# BD0004.net
KiCad netlist of a schematic drawn in EAGLE
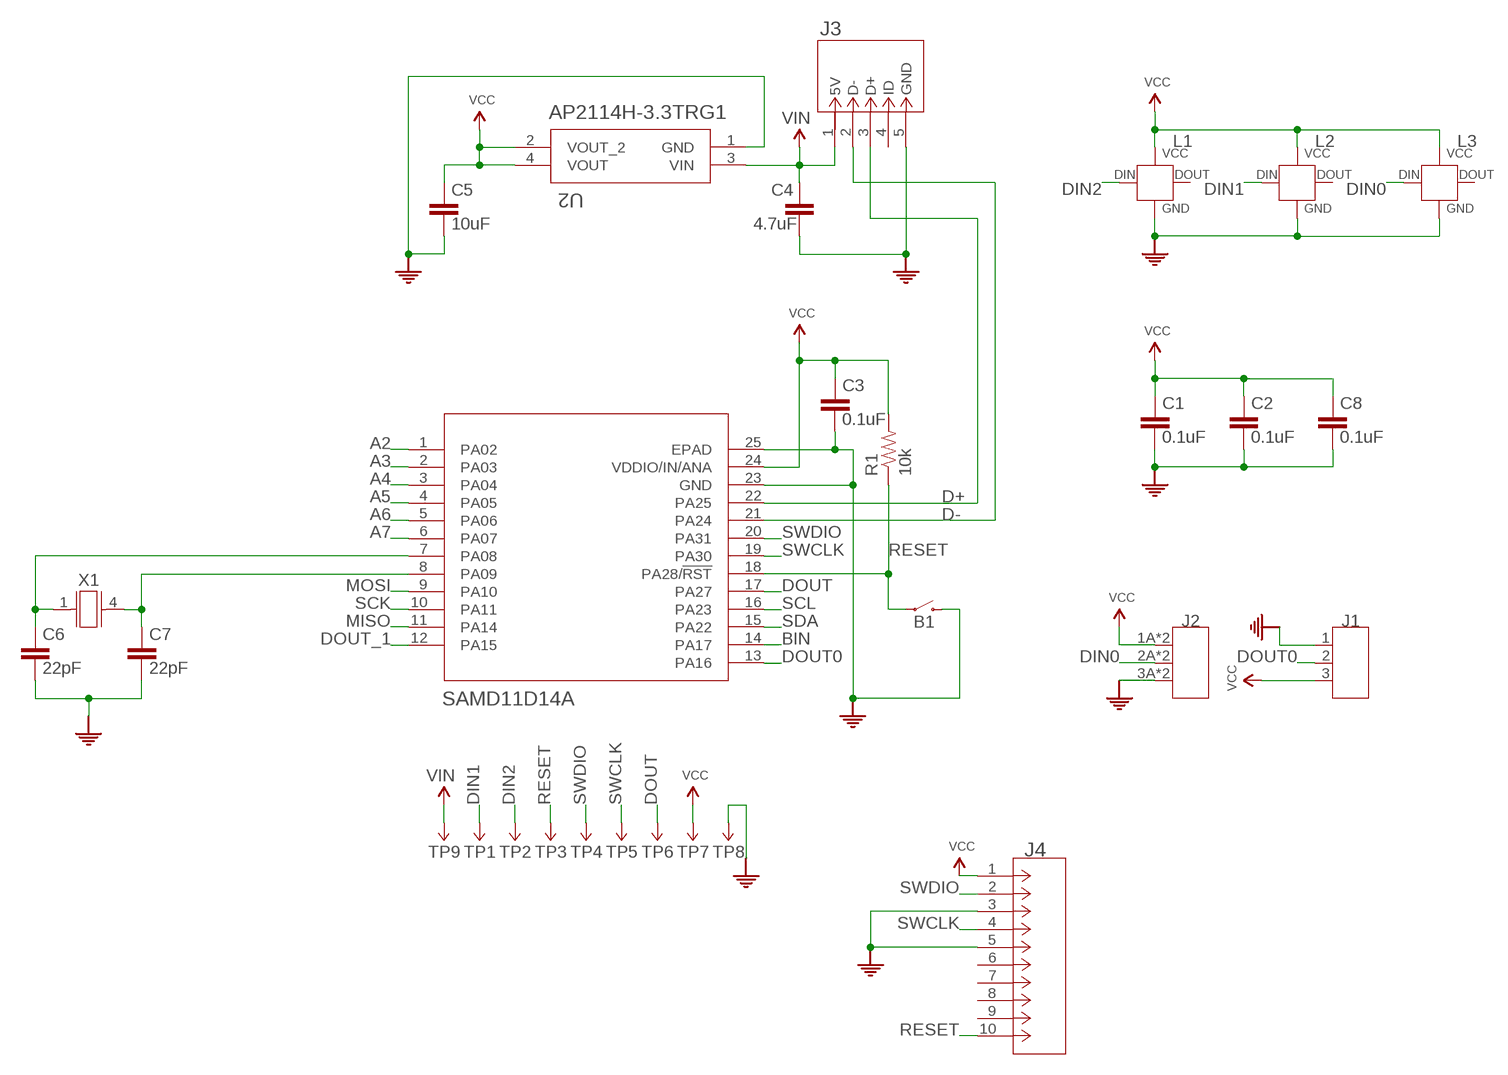
[diagram p0: schematic, sheet 1]

(export (version "E")
  (design (tool "Eeschema 10.0.6"))
  (components
    (comp (ref "B1")
      (value "EVQ-P7A01P")
      (footprint "eagle-import:4-SMD_BUTTON")
      (libsource (lib "eagle-import") (part "EVQ-P7A01P"))
    )
    (comp (ref "C1")
      (value "0.1uF")
      (footprint "eagle-import:0402")
      (libsource (lib "eagle-import") (part "CAPACITOR-0402"))
    )
    (comp (ref "C2")
      (value "0.1uF")
      (footprint "eagle-import:0402")
      (libsource (lib "eagle-import") (part "CAPACITOR-0402"))
    )
    (comp (ref "C3")
      (value "0.1uF")
      (footprint "eagle-import:0402")
      (libsource (lib "eagle-import") (part "CAPACITOR-0402"))
    )
    (comp (ref "C4")
      (value "4.7uF")
      (footprint "eagle-import:0402")
      (libsource (lib "eagle-import") (part "CAPACITOR-0402"))
    )
    (comp (ref "C5")
      (value "10uF")
      (footprint "eagle-import:0402")
      (libsource (lib "eagle-import") (part "CAPACITOR-0402"))
    )
    (comp (ref "C6")
      (value "22pF")
      (footprint "eagle-import:0402")
      (libsource (lib "eagle-import") (part "CAPACITOR-0402"))
    )
    (comp (ref "C7")
      (value "22pF")
      (footprint "eagle-import:0402")
      (libsource (lib "eagle-import") (part "CAPACITOR-0402"))
    )
    (comp (ref "C8")
      (value "0.1uF")
      (footprint "eagle-import:0402")
      (libsource (lib "eagle-import") (part "CAPACITOR-0402"))
    )
    (comp (ref "J1")
      (value "HEADER_1X3MALE")
      (footprint "eagle-import:M3SMD_RIGHTANGLE")
      (libsource (lib "eagle-import") (part "HEADER_1X3MALE"))
    )
    (comp (ref "J2")
      (value "HEADER_1X3FEMALE")
      (footprint "eagle-import:F3SMD_RIGHTANGLE")
      (libsource (lib "eagle-import") (part "HEADER_1X3FEMALE"))
    )
    (comp (ref "J3")
      (value "CONN_MICROUSB_FEMALE")
      (footprint "eagle-import:CON00679_5")
      (libsource (lib "eagle-import") (part "CONN_MICROUSB_FEMALE"))
    )
    (comp (ref "J4")
      (value "CORTEX-M_DEBUG_HEADER")
      (footprint "eagle-import:CONN_00010C4LF")
      (libsource (lib "eagle-import") (part "CORTEX-M_DEBUG_HEADER"))
    )
    (comp (ref "L1")
      (value "WS2812B-B")
      (footprint "eagle-import:SK6812-B")
      (libsource (lib "eagle-import") (part "WS2812B-B"))
    )
    (comp (ref "L2")
      (value "WS2812B-B")
      (footprint "eagle-import:SK6812-B")
      (libsource (lib "eagle-import") (part "WS2812B-B"))
    )
    (comp (ref "L3")
      (value "WS2812B-B")
      (footprint "eagle-import:SK6812-B")
      (libsource (lib "eagle-import") (part "WS2812B-B"))
    )
    (comp (ref "R1")
      (value "10k")
      (footprint "eagle-import:0402")
      (libsource (lib "eagle-import") (part "RESISTOR-0402"))
    )
    (comp (ref "TP1")
      (value "POGO")
      (footprint "eagle-import:R-1-CR")
      (libsource (lib "eagle-import") (part "POGO"))
    )
    (comp (ref "TP2")
      (value "POGO")
      (footprint "eagle-import:R-1-CR")
      (libsource (lib "eagle-import") (part "POGO"))
    )
    (comp (ref "TP3")
      (value "POGO")
      (footprint "eagle-import:R-1-CR")
      (libsource (lib "eagle-import") (part "POGO"))
    )
    (comp (ref "TP4")
      (value "POGO")
      (footprint "eagle-import:R-1-CR")
      (libsource (lib "eagle-import") (part "POGO"))
    )
    (comp (ref "TP5")
      (value "POGO")
      (footprint "eagle-import:R-1-CR")
      (libsource (lib "eagle-import") (part "POGO"))
    )
    (comp (ref "TP6")
      (value "POGO")
      (footprint "eagle-import:R-1-CR")
      (libsource (lib "eagle-import") (part "POGO"))
    )
    (comp (ref "TP7")
      (value "POGO")
      (footprint "eagle-import:R-1-CR")
      (libsource (lib "eagle-import") (part "POGO"))
    )
    (comp (ref "TP8")
      (value "POGO")
      (footprint "eagle-import:R-1-CR")
      (libsource (lib "eagle-import") (part "POGO"))
    )
    (comp (ref "TP9")
      (value "POGO")
      (footprint "eagle-import:R-1-CR")
      (libsource (lib "eagle-import") (part "POGO"))
    )
    (comp (ref "U1")
      (value "SAMD11D14A")
      (footprint "eagle-import:QFN24_4X4MC")
      (libsource (lib "eagle-import") (part "SAMD11D14A"))
    )
    (comp (ref "U2")
      (value "AP2114H-3.3TRG1")
      (footprint "eagle-import:SOT-223")
      (libsource (lib "eagle-import") (part "AP2114H-3.3TRG1"))
    )
    (comp (ref "X1")
      (value "MC-146-32.7680JKA-A0:ROHS")
      (footprint "eagle-import:4-SMD_FLAT_LEADS")
      (libsource (lib "eagle-import") (part "MC-146-32.7680JKA-A0{colon}ROHS"))
    )
  )
  (nets
    (net (code "1") (name "/A2") (class "Default")
      (node (ref "U1") (pin "1") (pinfunction "PA02_1") (pintype "bidirectional"))
    )
    (net (code "2") (name "/A3") (class "Default")
      (node (ref "U1") (pin "2") (pinfunction "PA03_2") (pintype "bidirectional"))
    )
    (net (code "3") (name "/A4") (class "Default")
      (node (ref "U1") (pin "3") (pinfunction "PA04_3") (pintype "bidirectional"))
    )
    (net (code "4") (name "/A5") (class "Default")
      (node (ref "U1") (pin "4") (pinfunction "PA05_4") (pintype "bidirectional"))
    )
    (net (code "5") (name "/A6") (class "Default")
      (node (ref "U1") (pin "5") (pinfunction "PA06_5") (pintype "bidirectional"))
    )
    (net (code "6") (name "/A7") (class "Default")
      (node (ref "U1") (pin "6") (pinfunction "PA07_6") (pintype "bidirectional"))
    )
    (net (code "7") (name "/BIN") (class "Default")
      (node (ref "U1") (pin "14") (pinfunction "PA17_14") (pintype "bidirectional"))
    )
    (net (code "8") (name "/D+") (class "Default")
      (node (ref "J3") (pin "3") (pinfunction "D+_3") (pintype "passive"))
      (node (ref "U1") (pin "22") (pinfunction "PA25_22") (pintype "bidirectional"))
    )
    (net (code "9") (name "/D-") (class "Default")
      (node (ref "J3") (pin "2") (pinfunction "D-_2") (pintype "passive"))
      (node (ref "U1") (pin "21") (pinfunction "PA24_21") (pintype "bidirectional"))
    )
    (net (code "10") (name "/DIN0") (class "Default")
      (node (ref "J2") (pin "2A") (pinfunction "P$2_2A") (pintype "bidirectional"))
      (node (ref "J2") (pin "2B") (pinfunction "P$2_2B") (pintype "bidirectional"))
      (node (ref "L3") (pin "2") (pinfunction "DIN_2") (pintype "bidirectional"))
    )
    (net (code "11") (name "/DIN1") (class "Default")
      (node (ref "L2") (pin "2") (pinfunction "DIN_2") (pintype "bidirectional"))
      (node (ref "TP1") (pin "P$1") (pinfunction "P$1_P$1") (pintype "bidirectional"))
    )
    (net (code "12") (name "/DIN2") (class "Default")
      (node (ref "L1") (pin "2") (pinfunction "DIN_2") (pintype "bidirectional"))
      (node (ref "TP2") (pin "P$1") (pinfunction "P$1_P$1") (pintype "bidirectional"))
    )
    (net (code "13") (name "/DOUT") (class "Default")
      (node (ref "TP6") (pin "P$1") (pinfunction "P$1_P$1") (pintype "bidirectional"))
      (node (ref "U1") (pin "17") (pinfunction "PA27_17") (pintype "bidirectional"))
    )
    (net (code "14") (name "/DOUT0") (class "Default")
      (node (ref "J1") (pin "2") (pinfunction "P$2_2") (pintype "bidirectional"))
      (node (ref "U1") (pin "13") (pinfunction "PA16_13") (pintype "bidirectional"))
    )
    (net (code "15") (name "/DOUT_1") (class "Default")
      (node (ref "U1") (pin "12") (pinfunction "PA15_12") (pintype "bidirectional"))
    )
    (net (code "16") (name "/MISO") (class "Default")
      (node (ref "U1") (pin "11") (pinfunction "PA14_11") (pintype "bidirectional"))
    )
    (net (code "17") (name "/MOSI") (class "Default")
      (node (ref "U1") (pin "9") (pinfunction "PA10_9") (pintype "bidirectional"))
    )
    (net (code "18") (name "/RESET") (class "Default")
      (node (ref "B1") (pin "1A") (pinfunction "P$1_1A") (pintype "bidirectional"))
      (node (ref "B1") (pin "1B") (pinfunction "P$1_1B") (pintype "bidirectional"))
      (node (ref "J4") (pin "10") (pinfunction "10_10") (pintype "passive"))
      (node (ref "R1") (pin "P$1") (pinfunction "1_P$1") (pintype "passive"))
      (node (ref "TP3") (pin "P$1") (pinfunction "P$1_P$1") (pintype "bidirectional"))
      (node (ref "U1") (pin "18") (pinfunction "PA28/~{RST}_18") (pintype "bidirectional"))
    )
    (net (code "19") (name "/SCK") (class "Default")
      (node (ref "U1") (pin "10") (pinfunction "PA11_10") (pintype "bidirectional"))
    )
    (net (code "20") (name "/SCL") (class "Default")
      (node (ref "U1") (pin "16") (pinfunction "PA23_16") (pintype "bidirectional"))
    )
    (net (code "21") (name "/SDA") (class "Default")
      (node (ref "U1") (pin "15") (pinfunction "PA22_15") (pintype "bidirectional"))
    )
    (net (code "22") (name "/SWCLK") (class "Default")
      (node (ref "J4") (pin "4") (pinfunction "4_4") (pintype "passive"))
      (node (ref "TP5") (pin "P$1") (pinfunction "P$1_P$1") (pintype "bidirectional"))
      (node (ref "U1") (pin "19") (pinfunction "PA30_19") (pintype "bidirectional"))
    )
    (net (code "23") (name "/SWDIO") (class "Default")
      (node (ref "J4") (pin "2") (pinfunction "2_2") (pintype "passive"))
      (node (ref "TP4") (pin "P$1") (pinfunction "P$1_P$1") (pintype "bidirectional"))
      (node (ref "U1") (pin "20") (pinfunction "PA31_20") (pintype "bidirectional"))
    )
    (net (code "24") (name "GND") (class "Default")
      (node (ref "B1") (pin "2A") (pinfunction "P$2_2A") (pintype "bidirectional"))
      (node (ref "B1") (pin "2B") (pinfunction "P$2_2B") (pintype "bidirectional"))
      (node (ref "C1") (pin "P$2") (pinfunction "2_P$2") (pintype "passive"))
      (node (ref "C2") (pin "P$2") (pinfunction "2_P$2") (pintype "passive"))
      (node (ref "C3") (pin "P$2") (pinfunction "2_P$2") (pintype "passive"))
      (node (ref "C4") (pin "P$2") (pinfunction "2_P$2") (pintype "passive"))
      (node (ref "C5") (pin "P$2") (pinfunction "2_P$2") (pintype "passive"))
      (node (ref "C6") (pin "P$2") (pinfunction "2_P$2") (pintype "passive"))
      (node (ref "C7") (pin "P$2") (pinfunction "2_P$2") (pintype "passive"))
      (node (ref "C8") (pin "P$2") (pinfunction "2_P$2") (pintype "passive"))
      (node (ref "J1") (pin "1") (pinfunction "P$1_1") (pintype "bidirectional"))
      (node (ref "J2") (pin "3A") (pinfunction "P$3_3A") (pintype "bidirectional"))
      (node (ref "J2") (pin "3B") (pinfunction "P$3_3B") (pintype "bidirectional"))
      (node (ref "J3") (pin "5") (pinfunction "GND_5") (pintype "passive"))
      (node (ref "J4") (pin "3") (pinfunction "3_3") (pintype "passive"))
      (node (ref "J4") (pin "5") (pinfunction "5_5") (pintype "passive"))
      (node (ref "L1") (pin "1") (pinfunction "VSS_1") (pintype "bidirectional"))
      (node (ref "L2") (pin "1") (pinfunction "VSS_1") (pintype "bidirectional"))
      (node (ref "L3") (pin "1") (pinfunction "VSS_1") (pintype "bidirectional"))
      (node (ref "TP8") (pin "P$1") (pinfunction "P$1_P$1") (pintype "bidirectional"))
      (node (ref "U1") (pin "23") (pinfunction "GND_23") (pintype "passive"))
      (node (ref "U1") (pin "25") (pinfunction "EPAD_25") (pintype "passive"))
      (node (ref "U2") (pin "1") (pinfunction "GND_1") (pintype "passive"))
    )
    (net (code "25") (name "Net-(C6-1)") (class "Default")
      (node (ref "C6") (pin "P$1") (pinfunction "1_P$1") (pintype "passive"))
      (node (ref "U1") (pin "7") (pinfunction "PA08_7") (pintype "bidirectional"))
      (node (ref "X1") (pin "1") (pinfunction "P$1_1") (pintype "bidirectional"))
    )
    (net (code "26") (name "Net-(C7-1)") (class "Default")
      (node (ref "C7") (pin "P$1") (pinfunction "1_P$1") (pintype "passive"))
      (node (ref "U1") (pin "8") (pinfunction "PA09_8") (pintype "bidirectional"))
      (node (ref "X1") (pin "4") (pinfunction "P$2_4") (pintype "bidirectional"))
    )
    (net (code "27") (name "VCC") (class "Default")
      (node (ref "C1") (pin "P$1") (pinfunction "1_P$1") (pintype "passive"))
      (node (ref "C2") (pin "P$1") (pinfunction "1_P$1") (pintype "passive"))
      (node (ref "C3") (pin "P$1") (pinfunction "1_P$1") (pintype "passive"))
      (node (ref "C5") (pin "P$1") (pinfunction "1_P$1") (pintype "passive"))
      (node (ref "C8") (pin "P$1") (pinfunction "1_P$1") (pintype "passive"))
      (node (ref "J1") (pin "3") (pinfunction "P$3_3") (pintype "bidirectional"))
      (node (ref "J2") (pin "1A") (pinfunction "P$1_1A") (pintype "bidirectional"))
      (node (ref "J2") (pin "1B") (pinfunction "P$1_1B") (pintype "bidirectional"))
      (node (ref "J4") (pin "1") (pinfunction "1_1") (pintype "passive"))
      (node (ref "L1") (pin "3") (pinfunction "VDD_3") (pintype "bidirectional"))
      (node (ref "L2") (pin "3") (pinfunction "VDD_3") (pintype "bidirectional"))
      (node (ref "L3") (pin "3") (pinfunction "VDD_3") (pintype "bidirectional"))
      (node (ref "R1") (pin "P$2") (pinfunction "2_P$2") (pintype "passive"))
      (node (ref "TP7") (pin "P$1") (pinfunction "P$1_P$1") (pintype "bidirectional"))
      (node (ref "U1") (pin "24") (pinfunction "VDDIO/IN/ANA_24") (pintype "power_in"))
      (node (ref "U2") (pin "2") (pinfunction "VOUT_2_2") (pintype "output"))
      (node (ref "U2") (pin "4") (pinfunction "VOUT_4") (pintype "output"))
    )
    (net (code "28") (name "VIN") (class "Default")
      (node (ref "C4") (pin "P$1") (pinfunction "1_P$1") (pintype "passive"))
      (node (ref "J3") (pin "1") (pinfunction "5V_1") (pintype "passive"))
      (node (ref "TP9") (pin "P$1") (pinfunction "P$1_P$1") (pintype "bidirectional"))
      (node (ref "U2") (pin "3") (pinfunction "VIN_3") (pintype "input"))
    )
    (net (code "29") (name "unconnected-(J3-ID-Pad4)") (class "Default")
      (node (ref "J3") (pin "4") (pinfunction "ID_4") (pintype "passive"))
    )
    (net (code "30") (name "unconnected-(J4-Pad6)") (class "Default")
      (node (ref "J4") (pin "6") (pinfunction "6_6") (pintype "passive"))
    )
    (net (code "31") (name "unconnected-(J4-Pad7)") (class "Default")
      (node (ref "J4") (pin "7") (pinfunction "7_7") (pintype "passive"))
    )
    (net (code "32") (name "unconnected-(J4-Pad8)") (class "Default")
      (node (ref "J4") (pin "8") (pinfunction "8_8") (pintype "passive"))
    )
    (net (code "33") (name "unconnected-(J4-Pad9)") (class "Default")
      (node (ref "J4") (pin "9") (pinfunction "9_9") (pintype "passive"))
    )
    (net (code "34") (name "unconnected-(L1-DOUT-Pad4)") (class "Default")
      (node (ref "L1") (pin "4") (pinfunction "DOUT_4") (pintype "bidirectional"))
    )
    (net (code "35") (name "unconnected-(L2-DOUT-Pad4)") (class "Default")
      (node (ref "L2") (pin "4") (pinfunction "DOUT_4") (pintype "bidirectional"))
    )
    (net (code "36") (name "unconnected-(L3-DOUT-Pad4)") (class "Default")
      (node (ref "L3") (pin "4") (pinfunction "DOUT_4") (pintype "bidirectional"))
    )
  )
)
